# 02-I_O.net
KiCad netlist of a schematic drawn in Altium Designer
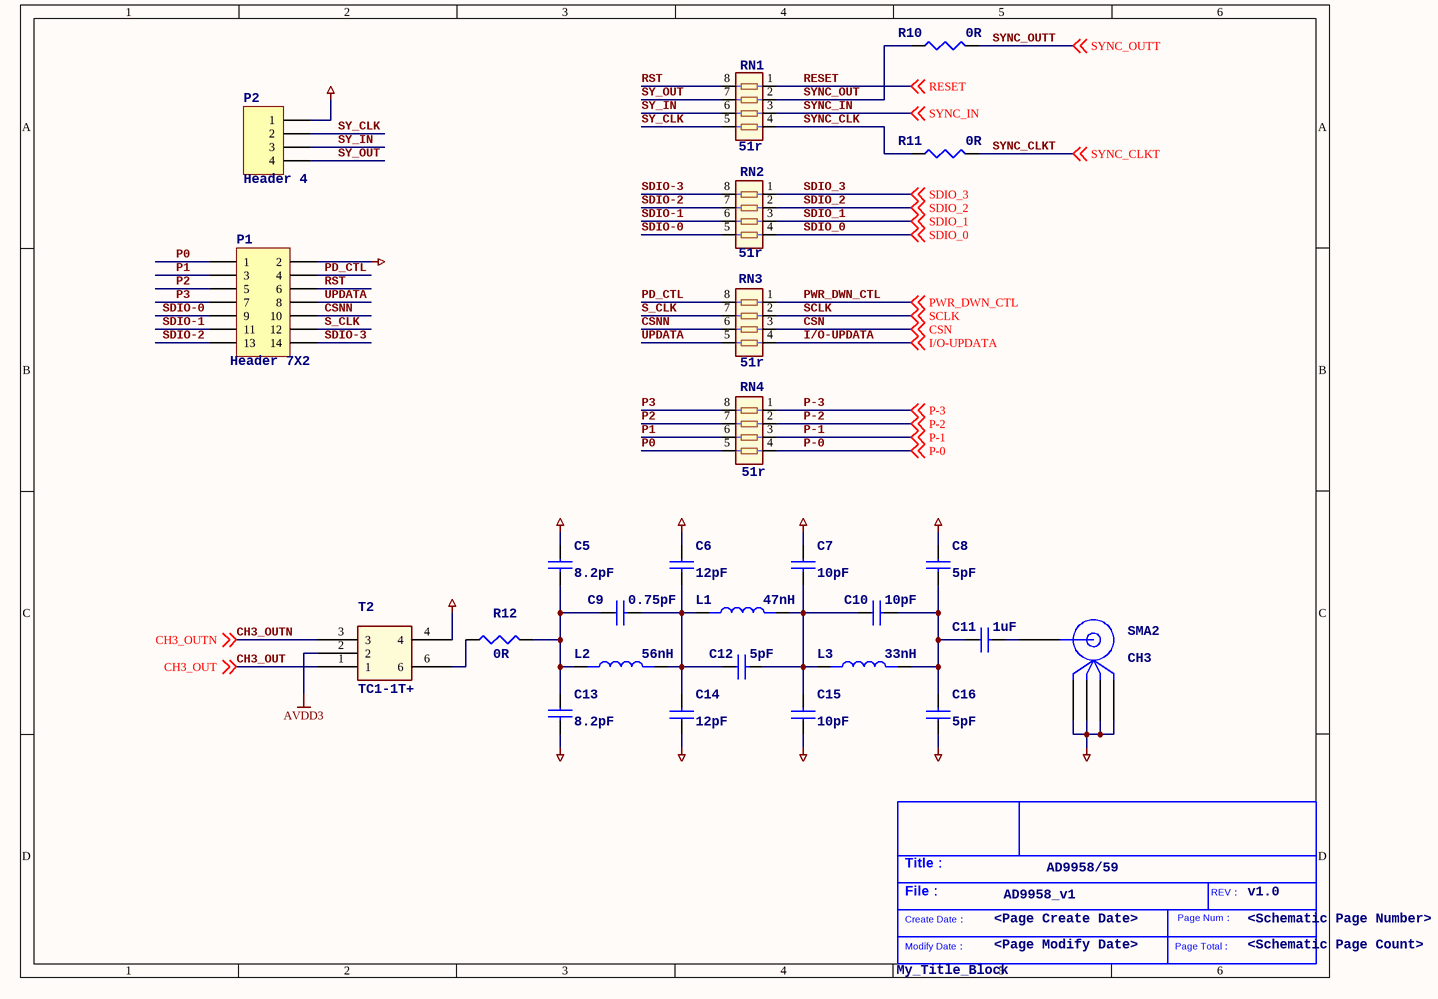
[diagram p0: 02-I_O.SchDoc]

(export (version "E")
  (design (tool "Eeschema 10.0.6"))
  (components
    (comp (ref "C5") (value "8.2pF") (footprint "0603C") (libsource (lib "*") (part "CAP NP")))
    (comp (ref "C6") (value "12pF") (footprint "0603C") (libsource (lib "*") (part "CAP NP")))
    (comp (ref "C7") (value "10pF") (footprint "0603C") (libsource (lib "*") (part "CAP NP")))
    (comp (ref "C8") (value "5pF") (footprint "0603C") (libsource (lib "*") (part "CAP NP")))
    (comp (ref "C9") (value "0.75pF") (footprint "0603C") (libsource (lib "*") (part "CAP NP")))
    (comp (ref "C10") (value "10pF") (footprint "0603C") (libsource (lib "*") (part "CAP NP")))
    (comp (ref "C11") (value "1uF") (footprint "0603C") (libsource (lib "*") (part "CAP NP")))
    (comp (ref "C12") (value "5pF") (footprint "0603C") (libsource (lib "*") (part "CAP NP")))
    (comp (ref "C13") (value "8.2pF") (footprint "0603C") (libsource (lib "*") (part "CAP NP")))
    (comp (ref "C14") (value "12pF") (footprint "0603C") (libsource (lib "*") (part "CAP NP")))
    (comp (ref "C15") (value "10pF") (footprint "0603C") (libsource (lib "*") (part "CAP NP")))
    (comp (ref "C16") (value "5pF") (footprint "0603C") (libsource (lib "*") (part "CAP NP")))
    (comp (ref "L1") (value "47nH") (footprint "0603L") (libsource (lib "*") (part "INDUCTANCE")))
    (comp (ref "L2") (value "56nH") (footprint "0603L") (libsource (lib "*") (part "INDUCTANCE")))
    (comp (ref "L3") (value "33nH") (footprint "0603L") (libsource (lib "*") (part "INDUCTANCE")))
    (comp (ref "P1")
      (value "Header 7X2")
      (footprint "CON20VP2R54-2X7TM-1")
      (description "Header, 7-Pin, Dual row")
      (fields (field (name "PUBLISHER") "Altium Limited"))
      (libsource (lib "Miscellaneous Connectors") (part "Header 7X2"))
    )
    (comp (ref "P2")
      (value "Header 4")
      (footprint "HDR1X4")
      (description "Header, 4-Pin")
      (fields (field (name "PUBLISHER") "Altium Limited"))
      (libsource (lib "Miscellaneous Connectors") (part "Header 4"))
    )
    (comp (ref "R10") (value "0R") (footprint "0603R") (libsource (lib "*") (part "R")))
    (comp (ref "R11") (value "0R") (footprint "0603R") (libsource (lib "*") (part "R")))
    (comp (ref "R12") (value "0R") (footprint "0603R") (libsource (lib "*") (part "R")))
    (comp (ref "RN1") (value "51r") (footprint "0603RA") (libsource (lib "*") (part "R_PACK_4")))
    (comp (ref "RN2") (value "51r") (footprint "0603RA") (libsource (lib "*") (part "R_PACK_4")))
    (comp (ref "RN3") (value "51r") (footprint "0603RA") (libsource (lib "*") (part "R_PACK_4")))
    (comp (ref "RN4") (value "51r") (footprint "0603RA") (libsource (lib "*") (part "R_PACK_4")))
    (comp (ref "SMA2") (value "CH3") (footprint "SMA-SMD") (libsource (lib "*") (part "BNC")))
    (comp (ref "T2") (value "TC1-1T+") (libsource (lib "*") (part "TC1-1T+")))
  )
  (nets
    (net (code "1") (name "/CSNN") (class "Default")
      (node (ref "P1") (pin "10") (pinfunction "10_10") (pintype "passive"))
      (node (ref "RN3") (pin "6") (pinfunction "6_6") (pintype "passive"))
    )
    (net (code "2") (name "/P0") (class "Default")
      (node (ref "P1") (pin "1") (pinfunction "1_1") (pintype "passive"))
      (node (ref "RN4") (pin "5") (pinfunction "5_5") (pintype "passive"))
    )
    (net (code "3") (name "/P1") (class "Default")
      (node (ref "P1") (pin "3") (pinfunction "3_3") (pintype "passive"))
      (node (ref "RN4") (pin "6") (pinfunction "6_6") (pintype "passive"))
    )
    (net (code "4") (name "/P2") (class "Default")
      (node (ref "P1") (pin "5") (pinfunction "5_5") (pintype "passive"))
      (node (ref "RN4") (pin "7") (pinfunction "7_7") (pintype "passive"))
    )
    (net (code "5") (name "/P3") (class "Default")
      (node (ref "P1") (pin "7") (pinfunction "7_7") (pintype "passive"))
      (node (ref "RN4") (pin "8") (pinfunction "8_8") (pintype "passive"))
    )
    (net (code "6") (name "/PD_CTL") (class "Default")
      (node (ref "P1") (pin "4") (pinfunction "4_4") (pintype "passive"))
      (node (ref "RN3") (pin "8") (pinfunction "8_8") (pintype "passive"))
    )
    (net (code "7") (name "/RST") (class "Default")
      (node (ref "P1") (pin "6") (pinfunction "6_6") (pintype "passive"))
      (node (ref "RN1") (pin "8") (pinfunction "8_8") (pintype "passive"))
    )
    (net (code "8") (name "/SDIO-0") (class "Default")
      (node (ref "P1") (pin "9") (pinfunction "9_9") (pintype "passive"))
      (node (ref "RN2") (pin "5") (pinfunction "5_5") (pintype "passive"))
    )
    (net (code "9") (name "/SDIO-1") (class "Default")
      (node (ref "P1") (pin "11") (pinfunction "11_11") (pintype "passive"))
      (node (ref "RN2") (pin "6") (pinfunction "6_6") (pintype "passive"))
    )
    (net (code "10") (name "/SDIO-2") (class "Default")
      (node (ref "P1") (pin "13") (pinfunction "13_13") (pintype "passive"))
      (node (ref "RN2") (pin "7") (pinfunction "7_7") (pintype "passive"))
    )
    (net (code "11") (name "/SDIO-3") (class "Default")
      (node (ref "P1") (pin "14") (pinfunction "14_14") (pintype "passive"))
      (node (ref "RN2") (pin "8") (pinfunction "8_8") (pintype "passive"))
    )
    (net (code "12") (name "/SYNC_CLK") (class "Default")
      (node (ref "R11") (pin "1") (pinfunction "1_1") (pintype "passive"))
      (node (ref "RN1") (pin "4") (pinfunction "4_4") (pintype "passive"))
    )
    (net (code "13") (name "/SYNC_OUT") (class "Default")
      (node (ref "R10") (pin "1") (pinfunction "1_1") (pintype "passive"))
      (node (ref "RN1") (pin "2") (pinfunction "2_2") (pintype "passive"))
    )
    (net (code "14") (name "/SY_CLK") (class "Default")
      (node (ref "P2") (pin "2") (pinfunction "2_2") (pintype "passive"))
      (node (ref "RN1") (pin "5") (pinfunction "5_5") (pintype "passive"))
    )
    (net (code "15") (name "/SY_IN") (class "Default")
      (node (ref "P2") (pin "3") (pinfunction "3_3") (pintype "passive"))
      (node (ref "RN1") (pin "6") (pinfunction "6_6") (pintype "passive"))
    )
    (net (code "16") (name "/SY_OUT") (class "Default")
      (node (ref "P2") (pin "4") (pinfunction "4_4") (pintype "passive"))
      (node (ref "RN1") (pin "7") (pinfunction "7_7") (pintype "passive"))
    )
    (net (code "17") (name "/S_CLK") (class "Default")
      (node (ref "P1") (pin "12") (pinfunction "12_12") (pintype "passive"))
      (node (ref "RN3") (pin "7") (pinfunction "7_7") (pintype "passive"))
    )
    (net (code "18") (name "/UPDATA") (class "Default")
      (node (ref "P1") (pin "8") (pinfunction "8_8") (pintype "passive"))
      (node (ref "RN3") (pin "5") (pinfunction "5_5") (pintype "passive"))
    )
    (net (code "19") (name "AGND") (class "Default")
      (node (ref "C13") (pin "2") (pinfunction "2_2") (pintype "passive"))
      (node (ref "C14") (pin "1") (pinfunction "1_1") (pintype "passive"))
      (node (ref "C15") (pin "1") (pinfunction "1_1") (pintype "passive"))
      (node (ref "C16") (pin "1") (pinfunction "1_1") (pintype "passive"))
      (node (ref "C5") (pin "1") (pinfunction "1_1") (pintype "passive"))
      (node (ref "C6") (pin "1") (pinfunction "1_1") (pintype "passive"))
      (node (ref "C7") (pin "1") (pinfunction "1_1") (pintype "passive"))
      (node (ref "C8") (pin "1") (pinfunction "1_1") (pintype "passive"))
      (node (ref "P1") (pin "2") (pinfunction "2_2") (pintype "passive"))
      (node (ref "P2") (pin "1") (pinfunction "1_1") (pintype "passive"))
      (node (ref "SMA2") (pin "2") (pinfunction "GND_2") (pintype "power_in"))
      (node (ref "SMA2") (pin "3") (pinfunction "GND_3") (pintype "power_in"))
      (node (ref "SMA2") (pin "4") (pinfunction "GND_4") (pintype "power_in"))
      (node (ref "SMA2") (pin "5") (pinfunction "GND_5") (pintype "power_in"))
      (node (ref "T2") (pin "4") (pinfunction "4_4") (pintype "passive"))
    )
    (net (code "20") (name "AVDD3") (class "Default")
      (node (ref "T2") (pin "2") (pinfunction "2_2") (pintype "passive"))
    )
    (net (code "21") (name "CH3_OUT") (class "Default")
      (node (ref "T2") (pin "1") (pinfunction "1_1") (pintype "passive"))
    )
    (net (code "22") (name "CH3_OUTN") (class "Default")
      (node (ref "T2") (pin "3") (pinfunction "3_3") (pintype "passive"))
    )
    (net (code "23") (name "CSN") (class "Default")
      (node (ref "RN3") (pin "3") (pinfunction "3_3") (pintype "passive"))
    )
    (net (code "24") (name "I{slash}O-UPDATA") (class "Default")
      (node (ref "RN3") (pin "4") (pinfunction "4_4") (pintype "passive"))
    )
    (net (code "25") (name "Net-(C10-Pad1)") (class "Default")
      (node (ref "C10") (pin "1") (pinfunction "1_1") (pintype "passive"))
      (node (ref "C12") (pin "2") (pinfunction "2_2") (pintype "passive"))
      (node (ref "C15") (pin "2") (pinfunction "2_2") (pintype "passive"))
      (node (ref "C7") (pin "2") (pinfunction "2_2") (pintype "passive"))
      (node (ref "L1") (pin "2") (pinfunction "2_2") (pintype "passive"))
      (node (ref "L3") (pin "1") (pinfunction "1_1") (pintype "passive"))
    )
    (net (code "26") (name "Net-(C10-Pad2)") (class "Default")
      (node (ref "C10") (pin "2") (pinfunction "2_2") (pintype "passive"))
      (node (ref "C11") (pin "1") (pinfunction "1_1") (pintype "passive"))
      (node (ref "C16") (pin "2") (pinfunction "2_2") (pintype "passive"))
      (node (ref "C8") (pin "2") (pinfunction "2_2") (pintype "passive"))
      (node (ref "L3") (pin "2") (pinfunction "2_2") (pintype "passive"))
    )
    (net (code "27") (name "Net-(C11-Pad2)") (class "Default")
      (node (ref "C11") (pin "2") (pinfunction "2_2") (pintype "passive"))
      (node (ref "SMA2") (pin "1") (pinfunction "1_1") (pintype "passive"))
    )
    (net (code "28") (name "Net-(C12-Pad1)") (class "Default")
      (node (ref "C12") (pin "1") (pinfunction "1_1") (pintype "passive"))
      (node (ref "C14") (pin "2") (pinfunction "2_2") (pintype "passive"))
      (node (ref "C6") (pin "2") (pinfunction "2_2") (pintype "passive"))
      (node (ref "C9") (pin "2") (pinfunction "2_2") (pintype "passive"))
      (node (ref "L1") (pin "1") (pinfunction "1_1") (pintype "passive"))
      (node (ref "L2") (pin "2") (pinfunction "2_2") (pintype "passive"))
    )
    (net (code "29") (name "Net-(C13-Pad1)") (class "Default")
      (node (ref "C13") (pin "1") (pinfunction "1_1") (pintype "passive"))
      (node (ref "C5") (pin "2") (pinfunction "2_2") (pintype "passive"))
      (node (ref "C9") (pin "1") (pinfunction "1_1") (pintype "passive"))
      (node (ref "L2") (pin "1") (pinfunction "1_1") (pintype "passive"))
      (node (ref "R12") (pin "2") (pinfunction "2_2") (pintype "passive"))
    )
    (net (code "30") (name "Net-(R12-Pad1)") (class "Default")
      (node (ref "R12") (pin "1") (pinfunction "1_1") (pintype "passive"))
      (node (ref "T2") (pin "6") (pinfunction "6_6") (pintype "passive"))
    )
    (net (code "31") (name "P-0") (class "Default")
      (node (ref "RN4") (pin "4") (pinfunction "4_4") (pintype "passive"))
    )
    (net (code "32") (name "P-1") (class "Default")
      (node (ref "RN4") (pin "3") (pinfunction "3_3") (pintype "passive"))
    )
    (net (code "33") (name "P-2") (class "Default")
      (node (ref "RN4") (pin "2") (pinfunction "2_2") (pintype "passive"))
    )
    (net (code "34") (name "P-3") (class "Default")
      (node (ref "RN4") (pin "1") (pinfunction "1_1") (pintype "passive"))
    )
    (net (code "35") (name "PWR_DWN_CTL") (class "Default")
      (node (ref "RN3") (pin "1") (pinfunction "1_1") (pintype "passive"))
    )
    (net (code "36") (name "RESET") (class "Default")
      (node (ref "RN1") (pin "1") (pinfunction "1_1") (pintype "passive"))
    )
    (net (code "37") (name "SCLK") (class "Default")
      (node (ref "RN3") (pin "2") (pinfunction "2_2") (pintype "passive"))
    )
    (net (code "38") (name "SDIO_0") (class "Default")
      (node (ref "RN2") (pin "4") (pinfunction "4_4") (pintype "passive"))
    )
    (net (code "39") (name "SDIO_1") (class "Default")
      (node (ref "RN2") (pin "3") (pinfunction "3_3") (pintype "passive"))
    )
    (net (code "40") (name "SDIO_2") (class "Default")
      (node (ref "RN2") (pin "2") (pinfunction "2_2") (pintype "passive"))
    )
    (net (code "41") (name "SDIO_3") (class "Default")
      (node (ref "RN2") (pin "1") (pinfunction "1_1") (pintype "passive"))
    )
    (net (code "42") (name "SYNC_CLKT") (class "Default")
      (node (ref "R11") (pin "2") (pinfunction "2_2") (pintype "passive"))
    )
    (net (code "43") (name "SYNC_IN") (class "Default")
      (node (ref "RN1") (pin "3") (pinfunction "3_3") (pintype "passive"))
    )
    (net (code "44") (name "SYNC_OUTT") (class "Default")
      (node (ref "R10") (pin "2") (pinfunction "2_2") (pintype "passive"))
    )
  )
)
